# SCH_Protection_Circuit_EasyEDA.net
KiCad netlist of a schematic drawn in EasyEDA
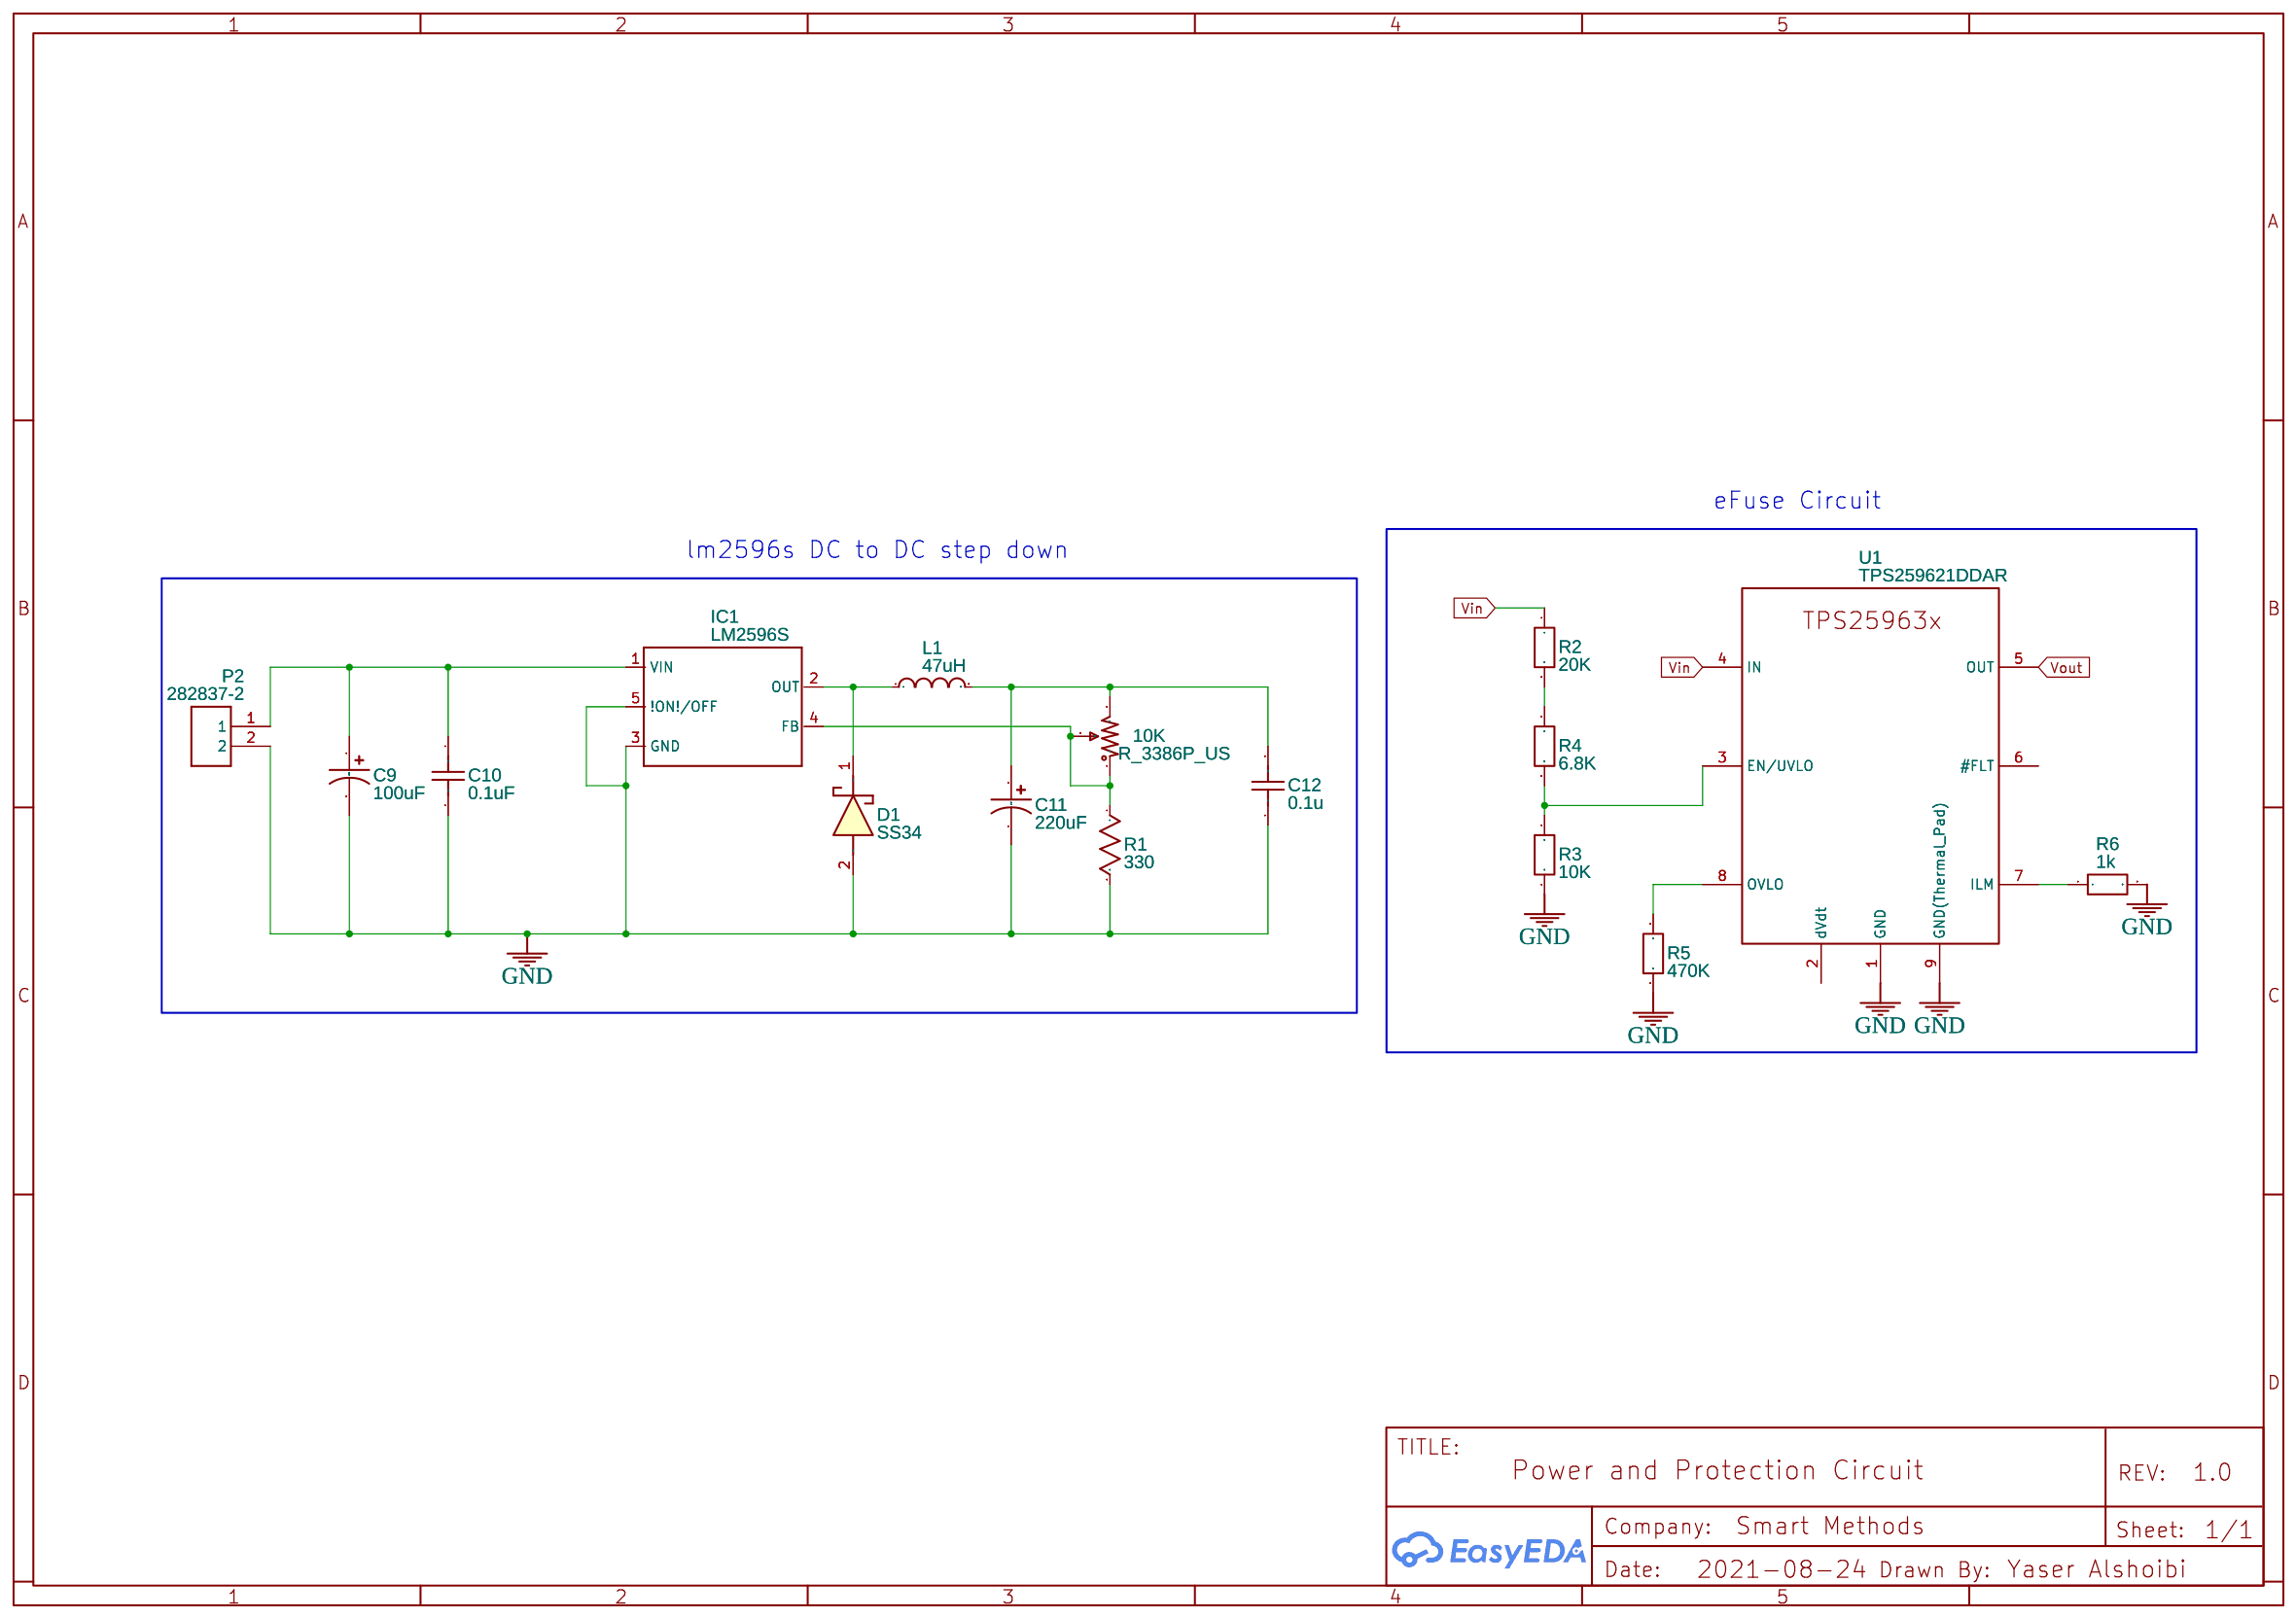
[diagram p0: schematic sheet]

(export (version "E")
  (design (tool "Eeschema 10.0.6"))
  (components
    (comp (ref "10K") (value "R_3386P_US") (libsource (lib "") (part "R_3386P_US")))
    (comp (ref "C9") (value "100uF") (libsource (lib "") (part "C_Tan_SMD_A_US_1")))
    (comp (ref "C10") (value "0.1uF") (libsource (lib "") (part "C_0603_US_1")))
    (comp (ref "C11") (value "220uF") (libsource (lib "") (part "C_Tan_SMD_A_US")))
    (comp (ref "C12") (value "0.1u") (libsource (lib "") (part "C_0603_US")))
    (comp (ref "D1") (value "SS34") (libsource (lib "") (part "SS34")))
    (comp (ref "IC1") (value "LM2596S") (libsource (lib "") (part "LM2596S")))
    (comp (ref "L1") (value "47uH") (libsource (lib "") (part "L0603_US")))
    (comp (ref "P2") (value "282837-2") (libsource (lib "") (part "282837-2")))
    (comp (ref "R1") (value "330") (libsource (lib "") (part "R_0603_US")))
    (comp (ref "R2") (value "20K") (libsource (lib "") (part "R_0603_EU_1")))
    (comp (ref "R3") (value "10K") (libsource (lib "") (part "R_0603_EU_1")))
    (comp (ref "R4") (value "6.8K") (libsource (lib "") (part "R_0603_EU_1")))
    (comp (ref "R5") (value "470K") (libsource (lib "") (part "R_0603_EU_2")))
    (comp (ref "R6") (value "1k") (libsource (lib "") (part "R_0603_EU")))
    (comp (ref "U1")
      (value "TPS259621DDAR")
      (fields (field (name "BOM_Supplier Part") "595-TPS259621DDAR"))
      (libsource (lib "") (part "TPS259621DDAR"))
    )
  )
  (nets
    (net (code "1") (name "GND") (class "Default")
      (node (ref "C10") (pin "2") (pinfunction "2_2") (pintype "unspecified"))
      (node (ref "C11") (pin "2") (pinfunction "2_2") (pintype "unspecified"))
      (node (ref "C12") (pin "1") (pinfunction "1_1") (pintype "unspecified"))
      (node (ref "C9") (pin "2") (pinfunction "2_2") (pintype "unspecified"))
      (node (ref "D1") (pin "2") (pinfunction "A_2") (pintype "bidirectional"))
      (node (ref "IC1") (pin "3") (pinfunction "GND_3") (pintype "bidirectional"))
      (node (ref "IC1") (pin "5") (pinfunction "!ON!/OFF_5") (pintype "bidirectional"))
      (node (ref "P2") (pin "2") (pinfunction "2_2") (pintype "bidirectional"))
      (node (ref "R1") (pin "2") (pinfunction "2_2") (pintype "unspecified"))
      (node (ref "R3") (pin "2") (pinfunction "2_2") (pintype "unspecified"))
      (node (ref "R5") (pin "1") (pinfunction "1_1") (pintype "unspecified"))
      (node (ref "R6") (pin "2") (pinfunction "2_2") (pintype "unspecified"))
      (node (ref "U1") (pin "1") (pinfunction "GND_1") (pintype "unspecified"))
      (node (ref "U1") (pin "9") (pinfunction "GND(Thermal_Pad)_9") (pintype "unspecified"))
    )
    (net (code "2") (name "Net-(10K-Pad3)") (class "Default")
      (node (ref "10K") (pin "3") (pinfunction "3_3") (pintype "unspecified"))
      (node (ref "C11") (pin "1") (pinfunction "1_1") (pintype "unspecified"))
      (node (ref "C12") (pin "2") (pinfunction "2_2") (pintype "unspecified"))
      (node (ref "L1") (pin "2") (pinfunction "2_2") (pintype "unspecified"))
    )
    (net (code "3") (name "Net-(D1-K)") (class "Default")
      (node (ref "D1") (pin "1") (pinfunction "K_1") (pintype "bidirectional"))
      (node (ref "IC1") (pin "2") (pinfunction "OUT_2") (pintype "bidirectional"))
      (node (ref "L1") (pin "1") (pinfunction "1_1") (pintype "unspecified"))
    )
    (net (code "4") (name "Net-(IC1-FB)") (class "Default")
      (node (ref "10K") (pin "1") (pinfunction "1_1") (pintype "unspecified"))
      (node (ref "10K") (pin "2") (pinfunction "2_2") (pintype "unspecified"))
      (node (ref "IC1") (pin "4") (pinfunction "FB_4") (pintype "bidirectional"))
      (node (ref "R1") (pin "1") (pinfunction "1_1") (pintype "unspecified"))
    )
    (net (code "5") (name "Net-(IC1-VIN)") (class "Default")
      (node (ref "C10") (pin "1") (pinfunction "1_1") (pintype "unspecified"))
      (node (ref "C9") (pin "1") (pinfunction "1_1") (pintype "unspecified"))
      (node (ref "IC1") (pin "1") (pinfunction "VIN_1") (pintype "bidirectional"))
      (node (ref "P2") (pin "1") (pinfunction "1_1") (pintype "bidirectional"))
    )
    (net (code "6") (name "Net-(R2-Pad2)") (class "Default")
      (node (ref "R2") (pin "2") (pinfunction "2_2") (pintype "unspecified"))
      (node (ref "R4") (pin "1") (pinfunction "1_1") (pintype "unspecified"))
    )
    (net (code "7") (name "Net-(U1-EN{slash}UVLO)") (class "Default")
      (node (ref "R3") (pin "1") (pinfunction "1_1") (pintype "unspecified"))
      (node (ref "R4") (pin "2") (pinfunction "2_2") (pintype "unspecified"))
      (node (ref "U1") (pin "3") (pinfunction "EN/UVLO_3") (pintype "unspecified"))
    )
    (net (code "8") (name "Net-(U1-ILM)") (class "Default")
      (node (ref "R6") (pin "1") (pinfunction "1_1") (pintype "unspecified"))
      (node (ref "U1") (pin "7") (pinfunction "ILM_7") (pintype "unspecified"))
    )
    (net (code "9") (name "Net-(U1-OVLO)") (class "Default")
      (node (ref "R5") (pin "2") (pinfunction "2_2") (pintype "unspecified"))
      (node (ref "U1") (pin "8") (pinfunction "OVLO_8") (pintype "unspecified"))
    )
    (net (code "10") (name "Vin") (class "Default")
      (node (ref "R2") (pin "1") (pinfunction "1_1") (pintype "unspecified"))
      (node (ref "U1") (pin "4") (pinfunction "IN_4") (pintype "unspecified"))
    )
    (net (code "11") (name "Vout") (class "Default")
      (node (ref "U1") (pin "5") (pinfunction "OUT_5") (pintype "unspecified"))
    )
    (net (code "12") (name "unconnected-(U1-#FLT-Pad6)") (class "Default")
      (node (ref "U1") (pin "6") (pinfunction "#FLT_6") (pintype "unspecified"))
    )
    (net (code "13") (name "unconnected-(U1-dVdt-Pad2)") (class "Default")
      (node (ref "U1") (pin "2") (pinfunction "dVdt_2") (pintype "unspecified"))
    )
  )
)
